# RK3562-USB-PCIe-PHY.net
KiCad netlist of a schematic drawn in Altium Designer
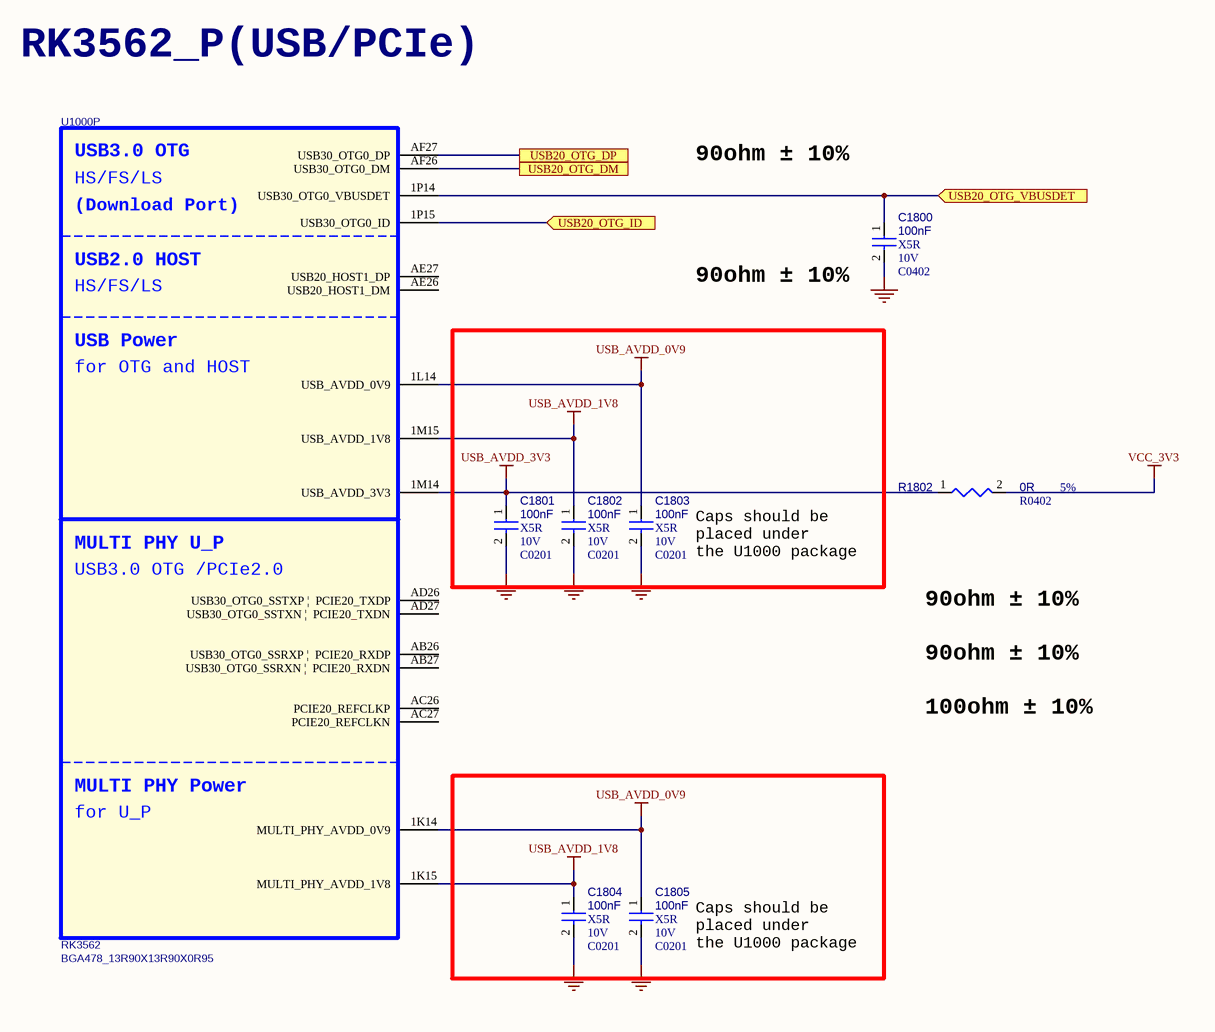
[diagram p0: RK3562-USB-PCIe-PHY.SchDoc]

(export (version "E")
  (design (tool "Eeschema 10.0.6"))
  (components
    (comp (ref "C1800")
      (value "100nF")
      (footprint "C0402")
      (description "cap,100.00nF,+/-10%,10V,X5R,C0402")
      (fields
        (field (name "DIELECTRIC") "X5R")
        (field (name "PCB FOOTPRINT") "C0402")
        (field (name "VOLTAGE") "10V")
        (field (name "MANUFACTURER") "TDK")
        (field (name "TOLERANCE") "10%")
        (field (name "CREATED BY") "JJJ")
      )
      (libsource (lib "RK3562_REF") (part "CAP NP"))
    )
    (comp (ref "C1801")
      (value "100nF")
      (footprint "C0201")
      (description "cap,100.00nF,+/-10%,10V,X5R,C0201")
      (fields
        (field (name "DIELECTRIC") "X5R")
        (field (name "PCB FOOTPRINT") "C0201")
        (field (name "VOLTAGE") "10V")
        (field (name "TOLERANCE") "10%")
        (field (name "MANUFACTURER") "TDK")
        (field (name "CREATED BY") "JJJ")
      )
      (libsource (lib "RK3562_REF") (part "CAP NP"))
    )
    (comp (ref "C1802")
      (value "100nF")
      (footprint "C0201")
      (description "cap,100.00nF,+/-10%,10V,X5R,C0201")
      (fields
        (field (name "DIELECTRIC") "X5R")
        (field (name "PCB FOOTPRINT") "C0201")
        (field (name "VOLTAGE") "10V")
        (field (name "TOLERANCE") "10%")
        (field (name "MANUFACTURER") "TDK")
        (field (name "CREATED BY") "JJJ")
      )
      (libsource (lib "RK3562_REF") (part "CAP NP"))
    )
    (comp (ref "C1803")
      (value "100nF")
      (footprint "C0201")
      (description "cap,100.00nF,+/-10%,10V,X5R,C0201")
      (fields
        (field (name "DIELECTRIC") "X5R")
        (field (name "PCB FOOTPRINT") "C0201")
        (field (name "VOLTAGE") "10V")
        (field (name "TOLERANCE") "10%")
        (field (name "MANUFACTURER") "TDK")
        (field (name "CREATED BY") "JJJ")
      )
      (libsource (lib "RK3562_REF") (part "CAP NP"))
    )
    (comp (ref "C1804")
      (value "100nF")
      (footprint "C0201")
      (description "cap,100.00nF,+/-10%,10V,X5R,C0201")
      (fields
        (field (name "DIELECTRIC") "X5R")
        (field (name "PCB FOOTPRINT") "C0201")
        (field (name "VOLTAGE") "10V")
        (field (name "TOLERANCE") "10%")
        (field (name "MANUFACTURER") "TDK")
        (field (name "CREATED BY") "JJJ")
      )
      (libsource (lib "RK3562_REF") (part "CAP NP"))
    )
    (comp (ref "C1805")
      (value "100nF")
      (footprint "C0201")
      (description "cap,100.00nF,+/-10%,10V,X5R,C0201")
      (fields
        (field (name "DIELECTRIC") "X5R")
        (field (name "PCB FOOTPRINT") "C0201")
        (field (name "VOLTAGE") "10V")
        (field (name "MANUFACTURER") "TDK")
        (field (name "TOLERANCE") "10%")
        (field (name "CREATED BY") "JJJ")
      )
      (libsource (lib "RK3562_REF") (part "CAP NP"))
    )
    (comp (ref "R1802")
      (value "0R")
      (footprint "R0402")
      (description "通用厚膜电阻,0R,+/-5%,R0402,1/16W.")
      (fields
        (field (name "TOLERANCE") "5%")
        (field (name "PCB FOOTPRINT") "R0402")
        (field (name "MANUFACTURER") "YAGEO")
        (field (name "CREATED BY") "YTL")
      )
      (libsource (lib "RK3562_REF") (part "RESISTOR"))
    )
    (comp (ref "U1000")
      (value "RK3562")
      (footprint "BGA478_13R90X13R90X0R95")
      (description "ROCKCHIP SOC")
      (fields
        (field (name "PCB FOOTPRINT") "BGA478_13R90X13R90X0R95")
        (field (name "MANUFACTURER") "Rockchip (瑞芯微)")
        (field (name "CREATED BY") "JJJ")
      )
      (libsource (lib "RK3562_REF") (part "SOC_RK3562"))
    )
  )
  (nets
    (net (code "1") (name "/USB20_OTG_DM") (class "Default")
      (node (ref "U1000") (pin "AF26") (pinfunction "USB30_OTG0_DM_AF26") (pintype "passive"))
    )
    (net (code "2") (name "/USB20_OTG_DP") (class "Default")
      (node (ref "U1000") (pin "AF27") (pinfunction "USB30_OTG0_DP_AF27") (pintype "passive"))
    )
    (net (code "3") (name "/USB20_OTG_ID") (class "Default")
      (node (ref "U1000") (pin "1P15") (pinfunction "USB30_OTG0_ID_1P15") (pintype "passive"))
    )
    (net (code "4") (name "/USB20_OTG_VBUSDET") (class "Default")
      (node (ref "C1800") (pin "1") (pinfunction "1_1") (pintype "passive"))
      (node (ref "U1000") (pin "1P14") (pinfunction "USB30_OTG0_VBUSDET_1P14") (pintype "passive"))
    )
    (net (code "5") (name "GND") (class "Default")
      (node (ref "C1800") (pin "2") (pinfunction "2_2") (pintype "passive"))
      (node (ref "C1801") (pin "2") (pinfunction "2_2") (pintype "passive"))
      (node (ref "C1802") (pin "2") (pinfunction "2_2") (pintype "passive"))
      (node (ref "C1803") (pin "2") (pinfunction "2_2") (pintype "passive"))
      (node (ref "C1804") (pin "2") (pinfunction "2_2") (pintype "passive"))
      (node (ref "C1805") (pin "2") (pinfunction "2_2") (pintype "passive"))
    )
    (net (code "6") (name "USB_AVDD_0V9") (class "Default")
      (node (ref "C1803") (pin "1") (pinfunction "1_1") (pintype "passive"))
      (node (ref "C1805") (pin "1") (pinfunction "1_1") (pintype "passive"))
      (node (ref "U1000") (pin "1K14") (pinfunction "MULTI_PHY_AVDD_0V9_1K14") (pintype "passive"))
      (node (ref "U1000") (pin "1L14") (pinfunction "USB_AVDD_0V9_1L14") (pintype "passive"))
    )
    (net (code "7") (name "USB_AVDD_1V8") (class "Default")
      (node (ref "C1802") (pin "1") (pinfunction "1_1") (pintype "passive"))
      (node (ref "C1804") (pin "1") (pinfunction "1_1") (pintype "passive"))
      (node (ref "U1000") (pin "1K15") (pinfunction "MULTI_PHY_AVDD_1V8_1K15") (pintype "passive"))
      (node (ref "U1000") (pin "1M15") (pinfunction "USB_AVDD_1V8_1M15") (pintype "passive"))
    )
    (net (code "8") (name "USB_AVDD_3V3") (class "Default")
      (node (ref "C1801") (pin "1") (pinfunction "1_1") (pintype "passive"))
      (node (ref "R1802") (pin "1") (pinfunction "1_1") (pintype "passive"))
      (node (ref "U1000") (pin "1M14") (pinfunction "USB_AVDD_3V3_1M14") (pintype "passive"))
    )
    (net (code "9") (name "VCC_3V3") (class "Default")
      (node (ref "R1802") (pin "2") (pinfunction "2_2") (pintype "passive"))
    )
    (net (code "10") (name "unconnected-(U1000P-PCIE20_REFCLKN-PadAC27)") (class "Default")
      (node (ref "U1000") (pin "AC27") (pinfunction "PCIE20_REFCLKN_AC27") (pintype "passive"))
    )
    (net (code "11") (name "unconnected-(U1000P-PCIE20_REFCLKP-PadAC26)") (class "Default")
      (node (ref "U1000") (pin "AC26") (pinfunction "PCIE20_REFCLKP_AC26") (pintype "passive"))
    )
    (net (code "12") (name "unconnected-(U1000P-USB20_HOST1_DM-PadAE26)") (class "Default")
      (node (ref "U1000") (pin "AE26") (pinfunction "USB20_HOST1_DM_AE26") (pintype "passive"))
    )
    (net (code "13") (name "unconnected-(U1000P-USB20_HOST1_DP-PadAE27)") (class "Default")
      (node (ref "U1000") (pin "AE27") (pinfunction "USB20_HOST1_DP_AE27") (pintype "passive"))
    )
    (net (code "14") (name "unconnected-(U1000P-USB30_OTG0_SSRXN_¦__PCIE20_RXDN-PadAB27)") (class "Default")
      (node (ref "U1000") (pin "AB27") (pinfunction "USB30_OTG0_SSRXN_¦__PCIE20_RXDN_AB27") (pintype "passive"))
    )
    (net (code "15") (name "unconnected-(U1000P-USB30_OTG0_SSRXP_¦__PCIE20_RXDP-PadAB26)") (class "Default")
      (node (ref "U1000") (pin "AB26") (pinfunction "USB30_OTG0_SSRXP_¦__PCIE20_RXDP_AB26") (pintype "passive"))
    )
    (net (code "16") (name "unconnected-(U1000P-USB30_OTG0_SSTXN_¦__PCIE20_TXDN-PadAD27)") (class "Default")
      (node (ref "U1000") (pin "AD27") (pinfunction "USB30_OTG0_SSTXN_¦__PCIE20_TXDN_AD27") (pintype "passive"))
    )
    (net (code "17") (name "unconnected-(U1000P-USB30_OTG0_SSTXP_¦__PCIE20_TXDP-PadAD26)") (class "Default")
      (node (ref "U1000") (pin "AD26") (pinfunction "USB30_OTG0_SSTXP_¦__PCIE20_TXDP_AD26") (pintype "passive"))
    )
  )
)
